# ADC_part1.net
KiCad netlist of a schematic drawn in Altium Designer
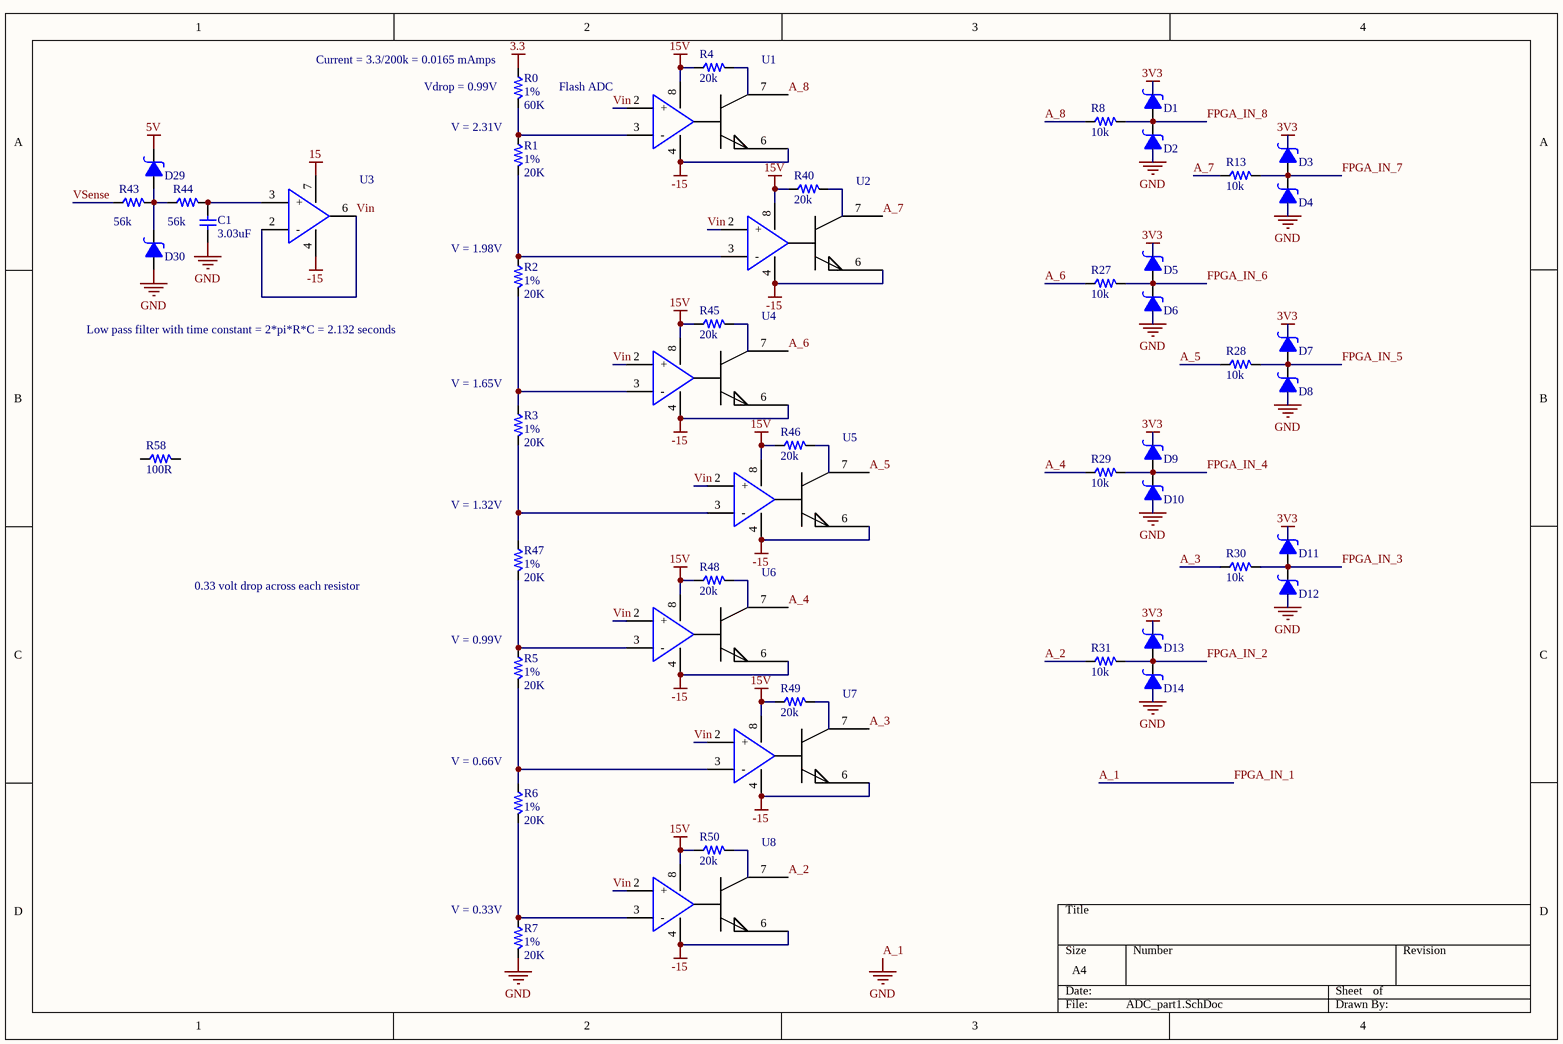
[diagram p0: ADC_part1.SchDoc]

(export (version "E")
  (design (tool "Eeschema 10.0.6"))
  (components
    (comp (ref "C1")
      (value "3.03uF")
      (footprint "PCB_GENERIC_SMD_0603")
      (description "CAP CER 0603 1uF 16V X5R 20%")
      (fields (field (name "TOLERANCE") "20%") (field (name "VOLTAGE") "16V"))
      (libsource (lib "CAP") (part "C060-0001U-00"))
    )
    (comp (ref "D1")
      (value "ONSEMI_MBRM110LT1G")
      (footprint "ON Semi Schottky Diode - MBRM110LT1G")
      (description "DIODE SCHOTTKY 10V 1A")
      (libsource (lib "ON Semi Schottky Diode") (part "ONSEMI_MBRM110LT1G"))
    )
    (comp (ref "D2")
      (value "ONSEMI_MBRM110LT1G")
      (footprint "ON Semi Schottky Diode - MBRM110LT1G")
      (description "DIODE SCHOTTKY 10V 1A")
      (libsource (lib "ON Semi Schottky Diode") (part "ONSEMI_MBRM110LT1G"))
    )
    (comp (ref "D3")
      (value "ONSEMI_MBRM110LT1G")
      (footprint "ON Semi Schottky Diode - MBRM110LT1G")
      (description "DIODE SCHOTTKY 10V 1A")
      (libsource (lib "ON Semi Schottky Diode") (part "ONSEMI_MBRM110LT1G"))
    )
    (comp (ref "D4")
      (value "ONSEMI_MBRM110LT1G")
      (footprint "ON Semi Schottky Diode - MBRM110LT1G")
      (description "DIODE SCHOTTKY 10V 1A")
      (libsource (lib "ON Semi Schottky Diode") (part "ONSEMI_MBRM110LT1G"))
    )
    (comp (ref "D5")
      (value "ONSEMI_MBRM110LT1G")
      (footprint "ON Semi Schottky Diode - MBRM110LT1G")
      (description "DIODE SCHOTTKY 10V 1A")
      (libsource (lib "ON Semi Schottky Diode") (part "ONSEMI_MBRM110LT1G"))
    )
    (comp (ref "D6")
      (value "ONSEMI_MBRM110LT1G")
      (footprint "ON Semi Schottky Diode - MBRM110LT1G")
      (description "DIODE SCHOTTKY 10V 1A")
      (libsource (lib "ON Semi Schottky Diode") (part "ONSEMI_MBRM110LT1G"))
    )
    (comp (ref "D7")
      (value "ONSEMI_MBRM110LT1G")
      (footprint "ON Semi Schottky Diode - MBRM110LT1G")
      (description "DIODE SCHOTTKY 10V 1A")
      (libsource (lib "ON Semi Schottky Diode") (part "ONSEMI_MBRM110LT1G"))
    )
    (comp (ref "D8")
      (value "ONSEMI_MBRM110LT1G")
      (footprint "ON Semi Schottky Diode - MBRM110LT1G")
      (description "DIODE SCHOTTKY 10V 1A")
      (libsource (lib "ON Semi Schottky Diode") (part "ONSEMI_MBRM110LT1G"))
    )
    (comp (ref "D9")
      (value "ONSEMI_MBRM110LT1G")
      (footprint "ON Semi Schottky Diode - MBRM110LT1G")
      (description "DIODE SCHOTTKY 10V 1A")
      (libsource (lib "ON Semi Schottky Diode") (part "ONSEMI_MBRM110LT1G"))
    )
    (comp (ref "D10")
      (value "ONSEMI_MBRM110LT1G")
      (footprint "ON Semi Schottky Diode - MBRM110LT1G")
      (description "DIODE SCHOTTKY 10V 1A")
      (libsource (lib "ON Semi Schottky Diode") (part "ONSEMI_MBRM110LT1G"))
    )
    (comp (ref "D11")
      (value "ONSEMI_MBRM110LT1G")
      (footprint "ON Semi Schottky Diode - MBRM110LT1G")
      (description "DIODE SCHOTTKY 10V 1A")
      (libsource (lib "ON Semi Schottky Diode") (part "ONSEMI_MBRM110LT1G"))
    )
    (comp (ref "D12")
      (value "ONSEMI_MBRM110LT1G")
      (footprint "ON Semi Schottky Diode - MBRM110LT1G")
      (description "DIODE SCHOTTKY 10V 1A")
      (libsource (lib "ON Semi Schottky Diode") (part "ONSEMI_MBRM110LT1G"))
    )
    (comp (ref "D13")
      (value "ONSEMI_MBRM110LT1G")
      (footprint "ON Semi Schottky Diode - MBRM110LT1G")
      (description "DIODE SCHOTTKY 10V 1A")
      (libsource (lib "ON Semi Schottky Diode") (part "ONSEMI_MBRM110LT1G"))
    )
    (comp (ref "D14")
      (value "ONSEMI_MBRM110LT1G")
      (footprint "ON Semi Schottky Diode - MBRM110LT1G")
      (description "DIODE SCHOTTKY 10V 1A")
      (libsource (lib "ON Semi Schottky Diode") (part "ONSEMI_MBRM110LT1G"))
    )
    (comp (ref "D29")
      (value "ONSEMI_MBRM110LT1G")
      (footprint "ON Semi Schottky Diode - MBRM110LT1G")
      (description "DIODE SCHOTTKY 10V 1A")
      (libsource (lib "ON Semi Schottky Diode") (part "ONSEMI_MBRM110LT1G"))
    )
    (comp (ref "D30")
      (value "ONSEMI_MBRM110LT1G")
      (footprint "ON Semi Schottky Diode - MBRM110LT1G")
      (description "DIODE SCHOTTKY 10V 1A")
      (libsource (lib "ON Semi Schottky Diode") (part "ONSEMI_MBRM110LT1G"))
    )
    (comp (ref "R0")
      (value "60K")
      (footprint "PCB_GENERIC_SMD_0603")
      (description "RES 0603 10K 1% 100mW")
      (fields
        (field (name "POWER") "100mW")
        (field (name "TOLERANCE") "1%")
        (field (name "Comment") "R060-00103-01")
      )
      (libsource (lib "RES") (part "R060-00103-01"))
    )
    (comp (ref "R1")
      (value "20K")
      (footprint "PCB_GENERIC_SMD_0603")
      (description "RES 0603 10K 1% 100mW")
      (fields
        (field (name "POWER") "100mW")
        (field (name "TOLERANCE") "1%")
        (field (name "Comment") "R060-00103-01")
      )
      (libsource (lib "RES") (part "R060-00103-01"))
    )
    (comp (ref "R2")
      (value "20K")
      (footprint "PCB_GENERIC_SMD_0603")
      (description "RES 0603 10K 1% 100mW")
      (fields
        (field (name "POWER") "100mW")
        (field (name "TOLERANCE") "1%")
        (field (name "Comment") "R060-00103-01")
      )
      (libsource (lib "RES") (part "R060-00103-01"))
    )
    (comp (ref "R3")
      (value "20K")
      (footprint "PCB_GENERIC_SMD_0603")
      (description "RES 0603 10K 1% 100mW")
      (fields
        (field (name "POWER") "100mW")
        (field (name "TOLERANCE") "1%")
        (field (name "Comment") "R060-00103-01")
      )
      (libsource (lib "RES") (part "R060-00103-01"))
    )
    (comp (ref "R4")
      (value "20k")
      (footprint "PCB_GENERIC_SMD_0603")
      (description "RES 0603 100ohm 5% 63mW")
      (fields (field (name "TOLERANCE") "5%") (field (name "POWER") "63mW"))
      (libsource (lib "RES") (part "R060-00101-05"))
    )
    (comp (ref "R5")
      (value "20K")
      (footprint "PCB_GENERIC_SMD_0603")
      (description "RES 0603 10K 1% 100mW")
      (fields
        (field (name "POWER") "100mW")
        (field (name "TOLERANCE") "1%")
        (field (name "Comment") "R060-00103-01")
      )
      (libsource (lib "RES") (part "R060-00103-01"))
    )
    (comp (ref "R6")
      (value "20K")
      (footprint "PCB_GENERIC_SMD_0603")
      (description "RES 0603 10K 1% 100mW")
      (fields
        (field (name "POWER") "100mW")
        (field (name "TOLERANCE") "1%")
        (field (name "Comment") "R060-00103-01")
      )
      (libsource (lib "RES") (part "R060-00103-01"))
    )
    (comp (ref "R7")
      (value "20K")
      (footprint "PCB_GENERIC_SMD_0603")
      (description "RES 0603 10K 1% 100mW")
      (fields
        (field (name "POWER") "100mW")
        (field (name "TOLERANCE") "1%")
        (field (name "Comment") "R060-00103-01")
      )
      (libsource (lib "RES") (part "R060-00103-01"))
    )
    (comp (ref "R8")
      (value "10k")
      (footprint "PCB_GENERIC_SMD_0603")
      (description "RES 0603 100ohm 5% 63mW")
      (fields (field (name "TOLERANCE") "5%") (field (name "POWER") "63mW"))
      (libsource (lib "RES") (part "R060-00101-05"))
    )
    (comp (ref "R13")
      (value "10k")
      (footprint "PCB_GENERIC_SMD_0603")
      (description "RES 0603 100ohm 5% 63mW")
      (fields (field (name "TOLERANCE") "5%") (field (name "POWER") "63mW"))
      (libsource (lib "RES") (part "R060-00101-05"))
    )
    (comp (ref "R27")
      (value "10k")
      (footprint "PCB_GENERIC_SMD_0603")
      (description "RES 0603 100ohm 5% 63mW")
      (fields (field (name "TOLERANCE") "5%") (field (name "POWER") "63mW"))
      (libsource (lib "RES") (part "R060-00101-05"))
    )
    (comp (ref "R28")
      (value "10k")
      (footprint "PCB_GENERIC_SMD_0603")
      (description "RES 0603 100ohm 5% 63mW")
      (fields (field (name "TOLERANCE") "5%") (field (name "POWER") "63mW"))
      (libsource (lib "RES") (part "R060-00101-05"))
    )
    (comp (ref "R29")
      (value "10k")
      (footprint "PCB_GENERIC_SMD_0603")
      (description "RES 0603 100ohm 5% 63mW")
      (fields (field (name "TOLERANCE") "5%") (field (name "POWER") "63mW"))
      (libsource (lib "RES") (part "R060-00101-05"))
    )
    (comp (ref "R30")
      (value "10k")
      (footprint "PCB_GENERIC_SMD_0603")
      (description "RES 0603 100ohm 5% 63mW")
      (fields (field (name "TOLERANCE") "5%") (field (name "POWER") "63mW"))
      (libsource (lib "RES") (part "R060-00101-05"))
    )
    (comp (ref "R31")
      (value "10k")
      (footprint "PCB_GENERIC_SMD_0603")
      (description "RES 0603 100ohm 5% 63mW")
      (fields (field (name "TOLERANCE") "5%") (field (name "POWER") "63mW"))
      (libsource (lib "RES") (part "R060-00101-05"))
    )
    (comp (ref "R40")
      (value "20k")
      (footprint "PCB_GENERIC_SMD_0603")
      (description "RES 0603 100ohm 5% 63mW")
      (fields (field (name "TOLERANCE") "5%") (field (name "POWER") "63mW"))
      (libsource (lib "RES") (part "R060-00101-05"))
    )
    (comp (ref "R43")
      (value "56k")
      (footprint "PCB_GENERIC_SMD_0603")
      (description "RES 0603 100ohm 5% 63mW")
      (fields (field (name "TOLERANCE") "5%") (field (name "POWER") "63mW"))
      (libsource (lib "RES") (part "R060-00101-05"))
    )
    (comp (ref "R44")
      (value "56k")
      (footprint "PCB_GENERIC_SMD_0603")
      (description "RES 0603 100ohm 5% 63mW")
      (fields (field (name "TOLERANCE") "5%") (field (name "POWER") "63mW"))
      (libsource (lib "RES") (part "R060-00101-05"))
    )
    (comp (ref "R45")
      (value "20k")
      (footprint "PCB_GENERIC_SMD_0603")
      (description "RES 0603 100ohm 5% 63mW")
      (fields (field (name "TOLERANCE") "5%") (field (name "POWER") "63mW"))
      (libsource (lib "RES") (part "R060-00101-05"))
    )
    (comp (ref "R46")
      (value "20k")
      (footprint "PCB_GENERIC_SMD_0603")
      (description "RES 0603 100ohm 5% 63mW")
      (fields (field (name "TOLERANCE") "5%") (field (name "POWER") "63mW"))
      (libsource (lib "RES") (part "R060-00101-05"))
    )
    (comp (ref "R47")
      (value "20K")
      (footprint "PCB_GENERIC_SMD_0603")
      (description "RES 0603 10K 1% 100mW")
      (fields
        (field (name "POWER") "100mW")
        (field (name "TOLERANCE") "1%")
        (field (name "Comment") "R060-00103-01")
      )
      (libsource (lib "RES") (part "R060-00103-01"))
    )
    (comp (ref "R48")
      (value "20k")
      (footprint "PCB_GENERIC_SMD_0603")
      (description "RES 0603 100ohm 5% 63mW")
      (fields (field (name "TOLERANCE") "5%") (field (name "POWER") "63mW"))
      (libsource (lib "RES") (part "R060-00101-05"))
    )
    (comp (ref "R49")
      (value "20k")
      (footprint "PCB_GENERIC_SMD_0603")
      (description "RES 0603 100ohm 5% 63mW")
      (fields (field (name "TOLERANCE") "5%") (field (name "POWER") "63mW"))
      (libsource (lib "RES") (part "R060-00101-05"))
    )
    (comp (ref "R50")
      (value "20k")
      (footprint "PCB_GENERIC_SMD_0603")
      (description "RES 0603 100ohm 5% 63mW")
      (fields (field (name "TOLERANCE") "5%") (field (name "POWER") "63mW"))
      (libsource (lib "RES") (part "R060-00101-05"))
    )
    (comp (ref "R58")
      (value "100R")
      (footprint "PCB_GENERIC_SMD_0603")
      (description "RES 0603 100ohm 5% 63mW")
      (fields (field (name "TOLERANCE") "5%") (field (name "POWER") "63mW"))
      (libsource (lib "RES") (part "R060-00101-05"))
    )
    (comp (ref "U1")
      (value "AP331A")
      (footprint "SOT95P285X130-5N")
      (description "Single Channel Comparator, Open Drain, SC-74A/SOT-753")
      (libsource (lib "Comparator") (part "AP331A"))
    )
    (comp (ref "U2")
      (value "AP331A")
      (footprint "SOT95P285X130-5N")
      (description "Single Channel Comparator, Open Drain, SC-74A/SOT-753")
      (libsource (lib "Comparator") (part "AP331A"))
    )
    (comp (ref "U3")
      (value "AP331A")
      (footprint "SOT95P285X130-5N")
      (description "Single Channel Comparator, Open Drain, SC-74A/SOT-753")
      (libsource (lib "Op_Amp") (part "AP331A"))
    )
    (comp (ref "U4")
      (value "AP331A")
      (footprint "SOT95P285X130-5N")
      (description "Single Channel Comparator, Open Drain, SC-74A/SOT-753")
      (libsource (lib "Comparator") (part "AP331A"))
    )
    (comp (ref "U5")
      (value "AP331A")
      (footprint "SOT95P285X130-5N")
      (description "Single Channel Comparator, Open Drain, SC-74A/SOT-753")
      (libsource (lib "Comparator") (part "AP331A"))
    )
    (comp (ref "U6")
      (value "AP331A")
      (footprint "SOT95P285X130-5N")
      (description "Single Channel Comparator, Open Drain, SC-74A/SOT-753")
      (libsource (lib "Comparator") (part "AP331A"))
    )
    (comp (ref "U7")
      (value "AP331A")
      (footprint "SOT95P285X130-5N")
      (description "Single Channel Comparator, Open Drain, SC-74A/SOT-753")
      (libsource (lib "Comparator") (part "AP331A"))
    )
    (comp (ref "U8")
      (value "AP331A")
      (footprint "SOT95P285X130-5N")
      (description "Single Channel Comparator, Open Drain, SC-74A/SOT-753")
      (libsource (lib "Comparator") (part "AP331A"))
    )
  )
  (nets
    (net (code "1") (name "-15") (class "Default")
      (node (ref "U1") (pin "4") (pinfunction "GND_4") (pintype "passive"))
      (node (ref "U1") (pin "6") (pinfunction "10_6") (pintype "passive"))
      (node (ref "U2") (pin "4") (pinfunction "GND_4") (pintype "passive"))
      (node (ref "U2") (pin "6") (pinfunction "10_6") (pintype "passive"))
      (node (ref "U3") (pin "4") (pinfunction "GND_4") (pintype "passive"))
      (node (ref "U4") (pin "4") (pinfunction "GND_4") (pintype "passive"))
      (node (ref "U4") (pin "6") (pinfunction "10_6") (pintype "passive"))
      (node (ref "U5") (pin "4") (pinfunction "GND_4") (pintype "passive"))
      (node (ref "U5") (pin "6") (pinfunction "10_6") (pintype "passive"))
      (node (ref "U6") (pin "4") (pinfunction "GND_4") (pintype "passive"))
      (node (ref "U6") (pin "6") (pinfunction "10_6") (pintype "passive"))
      (node (ref "U7") (pin "4") (pinfunction "GND_4") (pintype "passive"))
      (node (ref "U7") (pin "6") (pinfunction "10_6") (pintype "passive"))
      (node (ref "U8") (pin "4") (pinfunction "GND_4") (pintype "passive"))
      (node (ref "U8") (pin "6") (pinfunction "10_6") (pintype "passive"))
    )
    (net (code "2") (name "/A_2") (class "Default")
      (node (ref "R31") (pin "1") (pinfunction "1_1") (pintype "passive"))
      (node (ref "U8") (pin "7") (pinfunction "9_7") (pintype "passive"))
    )
    (net (code "3") (name "/A_3") (class "Default")
      (node (ref "R30") (pin "1") (pinfunction "1_1") (pintype "passive"))
      (node (ref "U7") (pin "7") (pinfunction "9_7") (pintype "passive"))
    )
    (net (code "4") (name "/A_4") (class "Default")
      (node (ref "R29") (pin "1") (pinfunction "1_1") (pintype "passive"))
      (node (ref "U6") (pin "7") (pinfunction "9_7") (pintype "passive"))
    )
    (net (code "5") (name "/A_5") (class "Default")
      (node (ref "R28") (pin "1") (pinfunction "1_1") (pintype "passive"))
      (node (ref "U5") (pin "7") (pinfunction "9_7") (pintype "passive"))
    )
    (net (code "6") (name "/A_6") (class "Default")
      (node (ref "R27") (pin "1") (pinfunction "1_1") (pintype "passive"))
      (node (ref "U4") (pin "7") (pinfunction "9_7") (pintype "passive"))
    )
    (net (code "7") (name "/A_7") (class "Default")
      (node (ref "R13") (pin "1") (pinfunction "1_1") (pintype "passive"))
      (node (ref "U2") (pin "7") (pinfunction "9_7") (pintype "passive"))
    )
    (net (code "8") (name "/A_8") (class "Default")
      (node (ref "R8") (pin "1") (pinfunction "1_1") (pintype "passive"))
      (node (ref "U1") (pin "7") (pinfunction "9_7") (pintype "passive"))
    )
    (net (code "9") (name "/FPGA_IN_2") (class "Default")
      (node (ref "D13") (pin "2") (pinfunction "2_2") (pintype "passive"))
      (node (ref "D14") (pin "1") (pinfunction "1_1") (pintype "passive"))
      (node (ref "R31") (pin "2") (pinfunction "2_2") (pintype "passive"))
    )
    (net (code "10") (name "/FPGA_IN_3") (class "Default")
      (node (ref "D11") (pin "2") (pinfunction "2_2") (pintype "passive"))
      (node (ref "D12") (pin "1") (pinfunction "1_1") (pintype "passive"))
      (node (ref "R30") (pin "2") (pinfunction "2_2") (pintype "passive"))
    )
    (net (code "11") (name "/FPGA_IN_4") (class "Default")
      (node (ref "D10") (pin "1") (pinfunction "1_1") (pintype "passive"))
      (node (ref "D9") (pin "2") (pinfunction "2_2") (pintype "passive"))
      (node (ref "R29") (pin "2") (pinfunction "2_2") (pintype "passive"))
    )
    (net (code "12") (name "/FPGA_IN_5") (class "Default")
      (node (ref "D7") (pin "2") (pinfunction "2_2") (pintype "passive"))
      (node (ref "D8") (pin "1") (pinfunction "1_1") (pintype "passive"))
      (node (ref "R28") (pin "2") (pinfunction "2_2") (pintype "passive"))
    )
    (net (code "13") (name "/FPGA_IN_6") (class "Default")
      (node (ref "D5") (pin "2") (pinfunction "2_2") (pintype "passive"))
      (node (ref "D6") (pin "1") (pinfunction "1_1") (pintype "passive"))
      (node (ref "R27") (pin "2") (pinfunction "2_2") (pintype "passive"))
    )
    (net (code "14") (name "/FPGA_IN_7") (class "Default")
      (node (ref "D3") (pin "2") (pinfunction "2_2") (pintype "passive"))
      (node (ref "D4") (pin "1") (pinfunction "1_1") (pintype "passive"))
      (node (ref "R13") (pin "2") (pinfunction "2_2") (pintype "passive"))
    )
    (net (code "15") (name "/FPGA_IN_8") (class "Default")
      (node (ref "D1") (pin "2") (pinfunction "2_2") (pintype "passive"))
      (node (ref "D2") (pin "1") (pinfunction "1_1") (pintype "passive"))
      (node (ref "R8") (pin "2") (pinfunction "2_2") (pintype "passive"))
    )
    (net (code "16") (name "/VSense") (class "Default")
      (node (ref "R43") (pin "1") (pinfunction "1_1") (pintype "passive"))
    )
    (net (code "17") (name "/Vin") (class "Default")
      (node (ref "U1") (pin "2") (pinfunction "+_2") (pintype "passive"))
      (node (ref "U2") (pin "2") (pinfunction "+_2") (pintype "passive"))
      (node (ref "U3") (pin "2") (pinfunction "-_2") (pintype "passive"))
      (node (ref "U3") (pin "6") (pinfunction "6_6") (pintype "passive"))
      (node (ref "U4") (pin "2") (pinfunction "+_2") (pintype "passive"))
      (node (ref "U5") (pin "2") (pinfunction "+_2") (pintype "passive"))
      (node (ref "U6") (pin "2") (pinfunction "+_2") (pintype "passive"))
      (node (ref "U7") (pin "2") (pinfunction "+_2") (pintype "passive"))
      (node (ref "U8") (pin "2") (pinfunction "+_2") (pintype "passive"))
    )
    (net (code "18") (name "3.3") (class "Default")
      (node (ref "R0") (pin "1") (pinfunction "1_1") (pintype "passive"))
    )
    (net (code "19") (name "3V3") (class "Default")
      (node (ref "D1") (pin "1") (pinfunction "1_1") (pintype "passive"))
      (node (ref "D11") (pin "1") (pinfunction "1_1") (pintype "passive"))
      (node (ref "D13") (pin "1") (pinfunction "1_1") (pintype "passive"))
      (node (ref "D3") (pin "1") (pinfunction "1_1") (pintype "passive"))
      (node (ref "D5") (pin "1") (pinfunction "1_1") (pintype "passive"))
      (node (ref "D7") (pin "1") (pinfunction "1_1") (pintype "passive"))
      (node (ref "D9") (pin "1") (pinfunction "1_1") (pintype "passive"))
    )
    (net (code "20") (name "5V") (class "Default")
      (node (ref "D29") (pin "1") (pinfunction "1_1") (pintype "passive"))
    )
    (net (code "21") (name "15") (class "Default")
      (node (ref "U3") (pin "7") (pinfunction "VCC_7") (pintype "passive"))
    )
    (net (code "22") (name "15V") (class "Default")
      (node (ref "R4") (pin "1") (pinfunction "1_1") (pintype "passive"))
      (node (ref "R40") (pin "1") (pinfunction "1_1") (pintype "passive"))
      (node (ref "R45") (pin "1") (pinfunction "1_1") (pintype "passive"))
      (node (ref "R46") (pin "1") (pinfunction "1_1") (pintype "passive"))
      (node (ref "R48") (pin "1") (pinfunction "1_1") (pintype "passive"))
      (node (ref "R49") (pin "1") (pinfunction "1_1") (pintype "passive"))
      (node (ref "R50") (pin "1") (pinfunction "1_1") (pintype "passive"))
      (node (ref "U1") (pin "8") (pinfunction "VCC_8") (pintype "passive"))
      (node (ref "U2") (pin "8") (pinfunction "VCC_8") (pintype "passive"))
      (node (ref "U4") (pin "8") (pinfunction "VCC_8") (pintype "passive"))
      (node (ref "U5") (pin "8") (pinfunction "VCC_8") (pintype "passive"))
      (node (ref "U6") (pin "8") (pinfunction "VCC_8") (pintype "passive"))
      (node (ref "U7") (pin "8") (pinfunction "VCC_8") (pintype "passive"))
      (node (ref "U8") (pin "8") (pinfunction "VCC_8") (pintype "passive"))
    )
    (net (code "23") (name "GND") (class "Default")
      (node (ref "C1") (pin "1") (pinfunction "1_1") (pintype "passive"))
      (node (ref "D10") (pin "2") (pinfunction "2_2") (pintype "passive"))
      (node (ref "D12") (pin "2") (pinfunction "2_2") (pintype "passive"))
      (node (ref "D14") (pin "2") (pinfunction "2_2") (pintype "passive"))
      (node (ref "D2") (pin "2") (pinfunction "2_2") (pintype "passive"))
      (node (ref "D30") (pin "2") (pinfunction "2_2") (pintype "passive"))
      (node (ref "D4") (pin "2") (pinfunction "2_2") (pintype "passive"))
      (node (ref "D6") (pin "2") (pinfunction "2_2") (pintype "passive"))
      (node (ref "D8") (pin "2") (pinfunction "2_2") (pintype "passive"))
      (node (ref "R7") (pin "2") (pinfunction "2_2") (pintype "passive"))
    )
    (net (code "24") (name "Net-(D29-Pad2)") (class "Default")
      (node (ref "D29") (pin "2") (pinfunction "2_2") (pintype "passive"))
      (node (ref "D30") (pin "1") (pinfunction "1_1") (pintype "passive"))
      (node (ref "R43") (pin "2") (pinfunction "2_2") (pintype "passive"))
      (node (ref "R44") (pin "1") (pinfunction "1_1") (pintype "passive"))
    )
    (net (code "25") (name "Net-(U1--)") (class "Default")
      (node (ref "R0") (pin "2") (pinfunction "2_2") (pintype "passive"))
      (node (ref "R1") (pin "1") (pinfunction "1_1") (pintype "passive"))
      (node (ref "U1") (pin "3") (pinfunction "-_3") (pintype "passive"))
    )
    (net (code "26") (name "Net-(U2--)") (class "Default")
      (node (ref "R1") (pin "2") (pinfunction "2_2") (pintype "passive"))
      (node (ref "R2") (pin "1") (pinfunction "1_1") (pintype "passive"))
      (node (ref "U2") (pin "3") (pinfunction "-_3") (pintype "passive"))
    )
    (net (code "27") (name "Net-(U3-+)") (class "Default")
      (node (ref "C1") (pin "2") (pinfunction "2_2") (pintype "passive"))
      (node (ref "R44") (pin "2") (pinfunction "2_2") (pintype "passive"))
      (node (ref "U3") (pin "3") (pinfunction "+_3") (pintype "passive"))
    )
    (net (code "28") (name "Net-(U4--)") (class "Default")
      (node (ref "R2") (pin "2") (pinfunction "2_2") (pintype "passive"))
      (node (ref "R3") (pin "1") (pinfunction "1_1") (pintype "passive"))
      (node (ref "U4") (pin "3") (pinfunction "-_3") (pintype "passive"))
    )
    (net (code "29") (name "Net-(U5--)") (class "Default")
      (node (ref "R3") (pin "2") (pinfunction "2_2") (pintype "passive"))
      (node (ref "R47") (pin "1") (pinfunction "1_1") (pintype "passive"))
      (node (ref "U5") (pin "3") (pinfunction "-_3") (pintype "passive"))
    )
    (net (code "30") (name "Net-(U6--)") (class "Default")
      (node (ref "R47") (pin "2") (pinfunction "2_2") (pintype "passive"))
      (node (ref "R5") (pin "1") (pinfunction "1_1") (pintype "passive"))
      (node (ref "U6") (pin "3") (pinfunction "-_3") (pintype "passive"))
    )
    (net (code "31") (name "Net-(U7--)") (class "Default")
      (node (ref "R5") (pin "2") (pinfunction "2_2") (pintype "passive"))
      (node (ref "R6") (pin "1") (pinfunction "1_1") (pintype "passive"))
      (node (ref "U7") (pin "3") (pinfunction "-_3") (pintype "passive"))
    )
    (net (code "32") (name "Net-(U8--)") (class "Default")
      (node (ref "R6") (pin "2") (pinfunction "2_2") (pintype "passive"))
      (node (ref "R7") (pin "1") (pinfunction "1_1") (pintype "passive"))
      (node (ref "U8") (pin "3") (pinfunction "-_3") (pintype "passive"))
    )
    (net (code "33") (name "unconnected-(R4-Pad2)") (class "Default")
      (node (ref "R4") (pin "2") (pinfunction "2_2") (pintype "passive"))
    )
    (net (code "34") (name "unconnected-(R40-Pad2)") (class "Default")
      (node (ref "R40") (pin "2") (pinfunction "2_2") (pintype "passive"))
    )
    (net (code "35") (name "unconnected-(R45-Pad2)") (class "Default")
      (node (ref "R45") (pin "2") (pinfunction "2_2") (pintype "passive"))
    )
    (net (code "36") (name "unconnected-(R46-Pad2)") (class "Default")
      (node (ref "R46") (pin "2") (pinfunction "2_2") (pintype "passive"))
    )
    (net (code "37") (name "unconnected-(R48-Pad2)") (class "Default")
      (node (ref "R48") (pin "2") (pinfunction "2_2") (pintype "passive"))
    )
    (net (code "38") (name "unconnected-(R49-Pad2)") (class "Default")
      (node (ref "R49") (pin "2") (pinfunction "2_2") (pintype "passive"))
    )
    (net (code "39") (name "unconnected-(R50-Pad2)") (class "Default")
      (node (ref "R50") (pin "2") (pinfunction "2_2") (pintype "passive"))
    )
    (net (code "40") (name "unconnected-(R58-Pad1)") (class "Default")
      (node (ref "R58") (pin "1") (pinfunction "1_1") (pintype "passive"))
    )
    (net (code "41") (name "unconnected-(R58-Pad2)") (class "Default")
      (node (ref "R58") (pin "2") (pinfunction "2_2") (pintype "passive"))
    )
  )
)
